# PasswordKeeper.net
KiCad netlist of a schematic drawn in EAGLE
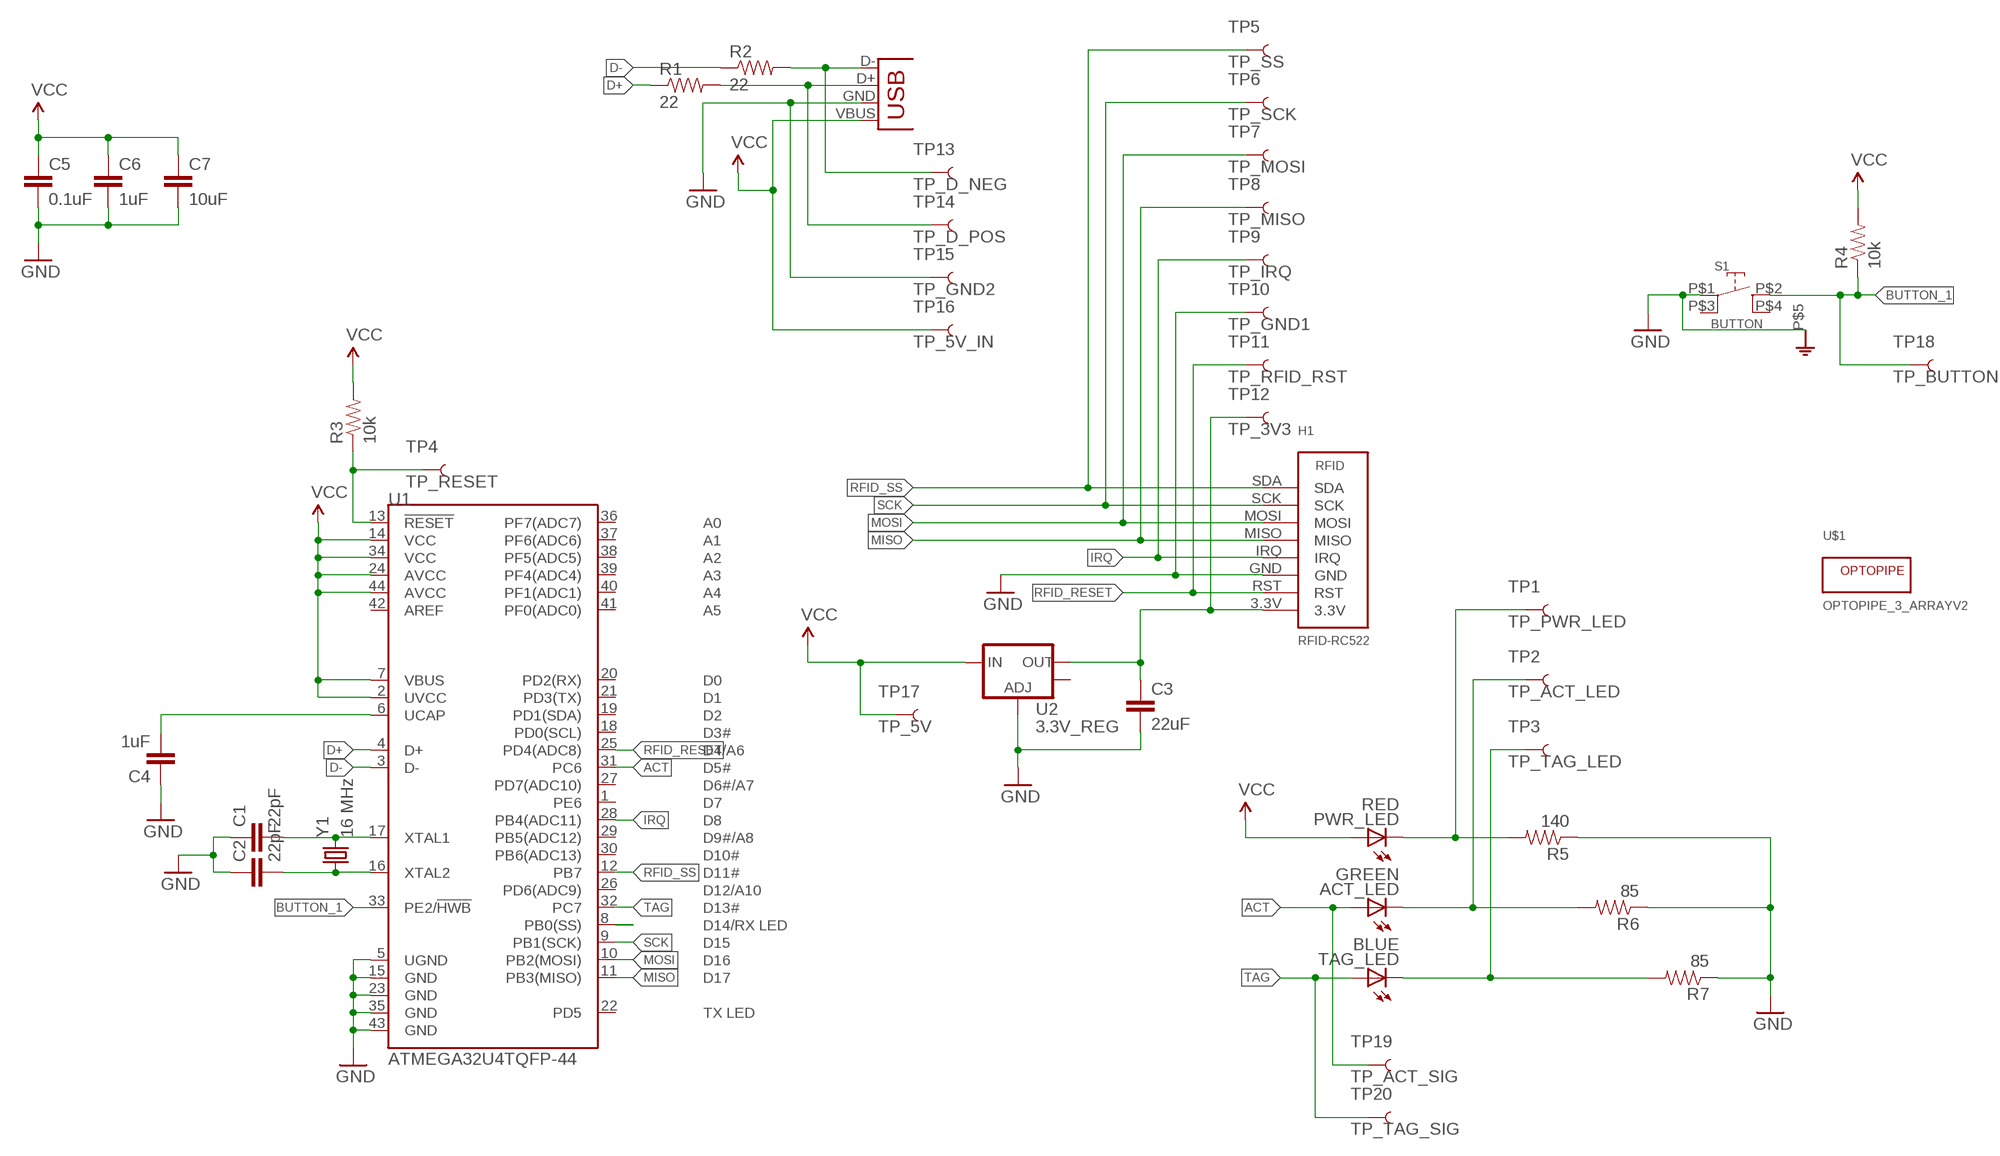
[diagram p0: schematic, sheet 1]

(export (version "E")
  (design (tool "Eeschema 10.0.6"))
  (components
    (comp (ref "ACT_LED")
      (value "GREEN")
      (footprint "eagle-import:LED-1206")
      (libsource (lib "eagle-import") (part "LED1206"))
    )
    (comp (ref "C1")
      (value "22pF")
      (footprint "eagle-import:1206")
      (libsource (lib "eagle-import") (part "CAP1206"))
    )
    (comp (ref "C2")
      (value "22pF")
      (footprint "eagle-import:1206")
      (libsource (lib "eagle-import") (part "CAP1206"))
    )
    (comp (ref "C3")
      (value "22uF")
      (footprint "eagle-import:0805")
      (libsource (lib "eagle-import") (part "22UF-0805-6.3V-20%"))
    )
    (comp (ref "C4")
      (value "1uF")
      (footprint "eagle-import:1206")
      (libsource (lib "eagle-import") (part "CAP1206"))
    )
    (comp (ref "C5")
      (value "0.1uF")
      (footprint "eagle-import:1206")
      (libsource (lib "eagle-import") (part "CAP1206"))
    )
    (comp (ref "C6")
      (value "1uF")
      (footprint "eagle-import:1206")
      (libsource (lib "eagle-import") (part "CAP1206"))
    )
    (comp (ref "C7")
      (value "10uF")
      (footprint "eagle-import:1206")
      (libsource (lib "eagle-import") (part "CAP1206"))
    )
    (comp (ref "H1")
      (value "RFID-RC522")
      (footprint "eagle-import:EXT_RFID_READER")
      (libsource (lib "eagle-import") (part "RFID-RC522"))
    )
    (comp (ref "JP1")
      (value "USB-A-H")
      (footprint "eagle-import:USB-A-H")
      (libsource (lib "eagle-import") (part "USB-A-H"))
    )
    (comp (ref "PWR_LED")
      (value "RED")
      (footprint "eagle-import:LED-1206")
      (libsource (lib "eagle-import") (part "LED1206"))
    )
    (comp (ref "R1")
      (value "22")
      (footprint "eagle-import:1206")
      (libsource (lib "eagle-import") (part "RESISTOR1206"))
    )
    (comp (ref "R2")
      (value "22")
      (footprint "eagle-import:1206")
      (libsource (lib "eagle-import") (part "RESISTOR1206"))
    )
    (comp (ref "R3")
      (value "10k")
      (footprint "eagle-import:1206")
      (libsource (lib "eagle-import") (part "RESISTOR1206"))
    )
    (comp (ref "R4")
      (value "10k")
      (footprint "eagle-import:1206")
      (libsource (lib "eagle-import") (part "RESISTOR1206"))
    )
    (comp (ref "R5")
      (value "140")
      (footprint "eagle-import:1206")
      (libsource (lib "eagle-import") (part "RESISTOR1206"))
    )
    (comp (ref "R6")
      (value "85")
      (footprint "eagle-import:1206")
      (libsource (lib "eagle-import") (part "RESISTOR1206"))
    )
    (comp (ref "R7")
      (value "85")
      (footprint "eagle-import:1206")
      (libsource (lib "eagle-import") (part "RESISTOR1206"))
    )
    (comp (ref "S1")
      (value "BUTTON")
      (footprint "eagle-import:TACTILE_SWITCH_SMD_RIGHT_ANGLE")
      (libsource (lib "eagle-import") (part "TACTILE_SWITCH_MOMENTARY_RIGHT_ANGLE"))
    )
    (comp (ref "TAG_LED")
      (value "BLUE")
      (footprint "eagle-import:LED-1206")
      (libsource (lib "eagle-import") (part "LED1206"))
    )
    (comp (ref "TP1")
      (value "TP_PWR_LED")
      (footprint "eagle-import:TP_15TH")
      (libsource (lib "eagle-import") (part "TEST-POINTTP_15TH_THRU"))
    )
    (comp (ref "TP2")
      (value "TP_ACT_LED")
      (footprint "eagle-import:TP_15TH")
      (libsource (lib "eagle-import") (part "TEST-POINTTP_15TH_THRU"))
    )
    (comp (ref "TP3")
      (value "TP_TAG_LED")
      (footprint "eagle-import:TP_15TH")
      (libsource (lib "eagle-import") (part "TEST-POINTTP_15TH_THRU"))
    )
    (comp (ref "TP4")
      (value "TP_RESET")
      (footprint "eagle-import:TP_15TH")
      (libsource (lib "eagle-import") (part "TEST-POINTTP_15TH_THRU"))
    )
    (comp (ref "TP5")
      (value "TP_SS")
      (footprint "eagle-import:TP_15TH")
      (libsource (lib "eagle-import") (part "TEST-POINTTP_15TH_THRU"))
    )
    (comp (ref "TP6")
      (value "TP_SCK")
      (footprint "eagle-import:TP_15TH")
      (libsource (lib "eagle-import") (part "TEST-POINTTP_15TH_THRU"))
    )
    (comp (ref "TP7")
      (value "TP_MOSI")
      (footprint "eagle-import:TP_15TH")
      (libsource (lib "eagle-import") (part "TEST-POINTTP_15TH_THRU"))
    )
    (comp (ref "TP8")
      (value "TP_MISO")
      (footprint "eagle-import:TP_15TH")
      (libsource (lib "eagle-import") (part "TEST-POINTTP_15TH_THRU"))
    )
    (comp (ref "TP9")
      (value "TP_IRQ")
      (footprint "eagle-import:TP_15TH")
      (libsource (lib "eagle-import") (part "TEST-POINTTP_15TH_THRU"))
    )
    (comp (ref "TP10")
      (value "TP_GND1")
      (footprint "eagle-import:TP_15TH")
      (libsource (lib "eagle-import") (part "TEST-POINTTP_15TH_THRU"))
    )
    (comp (ref "TP11")
      (value "TP_RFID_RST")
      (footprint "eagle-import:TP_15TH")
      (libsource (lib "eagle-import") (part "TEST-POINTTP_15TH_THRU"))
    )
    (comp (ref "TP12")
      (value "TP_3V3")
      (footprint "eagle-import:TP_15TH")
      (libsource (lib "eagle-import") (part "TEST-POINTTP_15TH_THRU"))
    )
    (comp (ref "TP13")
      (value "TP_D_NEG")
      (footprint "eagle-import:TP_15TH")
      (libsource (lib "eagle-import") (part "TEST-POINTTP_15TH_THRU"))
    )
    (comp (ref "TP14")
      (value "TP_D_POS")
      (footprint "eagle-import:TP_15TH")
      (libsource (lib "eagle-import") (part "TEST-POINTTP_15TH_THRU"))
    )
    (comp (ref "TP15")
      (value "TP_GND2")
      (footprint "eagle-import:TP_15TH")
      (libsource (lib "eagle-import") (part "TEST-POINTTP_15TH_THRU"))
    )
    (comp (ref "TP16")
      (value "TP_5V_IN")
      (footprint "eagle-import:TP_15TH")
      (libsource (lib "eagle-import") (part "TEST-POINTTP_15TH_THRU"))
    )
    (comp (ref "TP17")
      (value "TP_5V")
      (footprint "eagle-import:TP_15TH")
      (libsource (lib "eagle-import") (part "TEST-POINTTP_15TH_THRU"))
    )
    (comp (ref "TP18")
      (value "TP_BUTTON")
      (footprint "eagle-import:TP_15TH")
      (libsource (lib "eagle-import") (part "TEST-POINTTP_15TH_THRU"))
    )
    (comp (ref "TP19")
      (value "TP_ACT_SIG")
      (footprint "eagle-import:TP_15TH")
      (libsource (lib "eagle-import") (part "TEST-POINTTP_15TH_THRU"))
    )
    (comp (ref "TP20")
      (value "TP_TAG_SIG")
      (footprint "eagle-import:TP_15TH")
      (libsource (lib "eagle-import") (part "TEST-POINTTP_15TH_THRU"))
    )
    (comp (ref "U$1")
      (value "OPTOPIPE_3_ARRAYV2")
      (footprint "eagle-import:515-1000_V2")
      (libsource (lib "eagle-import") (part "OPTOPIPE_3_ARRAYV2"))
    )
    (comp (ref "U1")
      (value "ATMEGA32U4TQFP-44")
      (footprint "eagle-import:TQFP44")
      (libsource (lib "eagle-import") (part "ATMEGA32U4TQFP-44"))
    )
    (comp (ref "U2")
      (value "3.3V_REG")
      (footprint "eagle-import:SOT223")
      (libsource (lib "eagle-import") (part "V_REG_LM1117SOT223"))
    )
    (comp (ref "Y1")
      (value "16 MHz")
      (footprint "eagle-import:HC49UP")
      (libsource (lib "eagle-import") (part "CRYSTALSMD"))
    )
  )
  (nets
    (net (code "1") (name "ACT") (class "Default")
      (node (ref "ACT_LED") (pin "A") (pinfunction "A_A") (pintype "passive"))
      (node (ref "TP19") (pin "P$1") (pinfunction "1_P$1") (pintype "bidirectional"))
      (node (ref "U1") (pin "31") (pinfunction "PC6_31") (pintype "bidirectional"))
    )
    (net (code "2") (name "BUTTON_1") (class "Default")
      (node (ref "R4") (pin "1") (pinfunction "1_1") (pintype "passive"))
      (node (ref "S1") (pin "P$2") (pinfunction "P$2_P$2") (pintype "passive"))
      (node (ref "TP18") (pin "P$1") (pinfunction "1_P$1") (pintype "bidirectional"))
      (node (ref "U1") (pin "33") (pinfunction "PE2/~{HWB}_33") (pintype "bidirectional"))
    )
    (net (code "3") (name "D+") (class "Default")
      (node (ref "R1") (pin "1") (pinfunction "1_1") (pintype "passive"))
      (node (ref "U1") (pin "4") (pinfunction "D+_4") (pintype "bidirectional"))
    )
    (net (code "4") (name "D-") (class "Default")
      (node (ref "R2") (pin "1") (pinfunction "1_1") (pintype "passive"))
      (node (ref "U1") (pin "3") (pinfunction "D-_3") (pintype "bidirectional"))
    )
    (net (code "5") (name "GND") (class "Default")
      (node (ref "C1") (pin "1") (pinfunction "1_1") (pintype "passive"))
      (node (ref "C2") (pin "1") (pinfunction "1_1") (pintype "passive"))
      (node (ref "C3") (pin "2") (pinfunction "2_2") (pintype "passive"))
      (node (ref "C4") (pin "1") (pinfunction "1_1") (pintype "passive"))
      (node (ref "C5") (pin "2") (pinfunction "2_2") (pintype "passive"))
      (node (ref "C6") (pin "2") (pinfunction "2_2") (pintype "passive"))
      (node (ref "C7") (pin "2") (pinfunction "2_2") (pintype "passive"))
      (node (ref "H1") (pin "GND") (pinfunction "GND_GND") (pintype "bidirectional"))
      (node (ref "JP1") (pin "GND") (pinfunction "VBUS_GND") (pintype "bidirectional"))
      (node (ref "R5") (pin "1") (pinfunction "1_1") (pintype "passive"))
      (node (ref "R6") (pin "1") (pinfunction "1_1") (pintype "passive"))
      (node (ref "R7") (pin "1") (pinfunction "1_1") (pintype "passive"))
      (node (ref "S1") (pin "P$1") (pinfunction "P$1_P$1") (pintype "passive"))
      (node (ref "S1") (pin "P$5") (pinfunction "P$5_P$5") (pintype "bidirectional"))
      (node (ref "TP10") (pin "P$1") (pinfunction "1_P$1") (pintype "bidirectional"))
      (node (ref "TP15") (pin "P$1") (pinfunction "1_P$1") (pintype "bidirectional"))
      (node (ref "U1") (pin "15") (pinfunction "GND_15") (pintype "bidirectional"))
      (node (ref "U1") (pin "23") (pinfunction "GND_23") (pintype "bidirectional"))
      (node (ref "U1") (pin "35") (pinfunction "GND_35") (pintype "bidirectional"))
      (node (ref "U1") (pin "43") (pinfunction "GND_43") (pintype "bidirectional"))
      (node (ref "U1") (pin "5") (pinfunction "UGND_5") (pintype "bidirectional"))
      (node (ref "U2") (pin "1") (pinfunction "ADJ_1") (pintype "input"))
    )
    (net (code "6") (name "IRQ") (class "Default")
      (node (ref "H1") (pin "IRQ") (pinfunction "IRQ_IRQ") (pintype "bidirectional"))
      (node (ref "TP9") (pin "P$1") (pinfunction "1_P$1") (pintype "bidirectional"))
      (node (ref "U1") (pin "28") (pinfunction "PB4(ADC11)_28") (pintype "bidirectional"))
    )
    (net (code "7") (name "MISO") (class "Default")
      (node (ref "H1") (pin "MISO") (pinfunction "MISO_MISO") (pintype "bidirectional"))
      (node (ref "TP8") (pin "P$1") (pinfunction "1_P$1") (pintype "bidirectional"))
      (node (ref "U1") (pin "11") (pinfunction "PB3(MISO)_11") (pintype "bidirectional"))
    )
    (net (code "8") (name "MOSI") (class "Default")
      (node (ref "H1") (pin "MOSI") (pinfunction "MOSI_MOSI") (pintype "bidirectional"))
      (node (ref "TP7") (pin "P$1") (pinfunction "1_P$1") (pintype "bidirectional"))
      (node (ref "U1") (pin "10") (pinfunction "PB2(MOSI)_10") (pintype "bidirectional"))
    )
    (net (code "9") (name "Net-(JP1-D+)") (class "Default")
      (node (ref "JP1") (pin "D-") (pinfunction "D+_D-") (pintype "bidirectional"))
      (node (ref "R2") (pin "2") (pinfunction "2_2") (pintype "passive"))
      (node (ref "TP13") (pin "P$1") (pinfunction "1_P$1") (pintype "bidirectional"))
    )
    (net (code "10") (name "Net-(JP1-D-)") (class "Default")
      (node (ref "JP1") (pin "D+") (pinfunction "D-_D+") (pintype "bidirectional"))
      (node (ref "R1") (pin "2") (pinfunction "2_2") (pintype "passive"))
      (node (ref "TP14") (pin "P$1") (pinfunction "1_P$1") (pintype "bidirectional"))
    )
    (net (code "11") (name "Net-(TP1-1)") (class "Default")
      (node (ref "PWR_LED") (pin "C") (pinfunction "C_C") (pintype "passive"))
      (node (ref "R5") (pin "2") (pinfunction "2_2") (pintype "passive"))
      (node (ref "TP1") (pin "P$1") (pinfunction "1_P$1") (pintype "bidirectional"))
    )
    (net (code "12") (name "Net-(TP2-1)") (class "Default")
      (node (ref "ACT_LED") (pin "C") (pinfunction "C_C") (pintype "passive"))
      (node (ref "R6") (pin "2") (pinfunction "2_2") (pintype "passive"))
      (node (ref "TP2") (pin "P$1") (pinfunction "1_P$1") (pintype "bidirectional"))
    )
    (net (code "13") (name "Net-(TP3-1)") (class "Default")
      (node (ref "R7") (pin "2") (pinfunction "2_2") (pintype "passive"))
      (node (ref "TAG_LED") (pin "C") (pinfunction "C_C") (pintype "passive"))
      (node (ref "TP3") (pin "P$1") (pinfunction "1_P$1") (pintype "bidirectional"))
    )
    (net (code "14") (name "Net-(TP4-1)") (class "Default")
      (node (ref "R3") (pin "1") (pinfunction "1_1") (pintype "passive"))
      (node (ref "TP4") (pin "P$1") (pinfunction "1_P$1") (pintype "bidirectional"))
      (node (ref "U1") (pin "13") (pinfunction "~{RESET}_13") (pintype "bidirectional"))
    )
    (net (code "15") (name "Net-(TP12-1)") (class "Default")
      (node (ref "C3") (pin "1") (pinfunction "1_1") (pintype "passive"))
      (node (ref "H1") (pin "3.3V") (pinfunction "3.3V_3.3V") (pintype "bidirectional"))
      (node (ref "TP12") (pin "P$1") (pinfunction "1_P$1") (pintype "bidirectional"))
      (node (ref "U2") (pin "2") (pinfunction "OUT_2") (pintype "output"))
    )
    (net (code "16") (name "Net-(U1-UCAP)") (class "Default")
      (node (ref "C4") (pin "2") (pinfunction "2_2") (pintype "passive"))
      (node (ref "U1") (pin "6") (pinfunction "UCAP_6") (pintype "bidirectional"))
    )
    (net (code "17") (name "Net-(U1-XTAL1)") (class "Default")
      (node (ref "C1") (pin "2") (pinfunction "2_2") (pintype "passive"))
      (node (ref "U1") (pin "17") (pinfunction "XTAL1_17") (pintype "bidirectional"))
      (node (ref "Y1") (pin "2") (pinfunction "2_2") (pintype "passive"))
    )
    (net (code "18") (name "Net-(U1-XTAL2)") (class "Default")
      (node (ref "C2") (pin "2") (pinfunction "2_2") (pintype "passive"))
      (node (ref "U1") (pin "16") (pinfunction "XTAL2_16") (pintype "bidirectional"))
      (node (ref "Y1") (pin "1") (pinfunction "1_1") (pintype "passive"))
    )
    (net (code "19") (name "RFID_RESET") (class "Default")
      (node (ref "H1") (pin "RST") (pinfunction "RST_RST") (pintype "bidirectional"))
      (node (ref "TP11") (pin "P$1") (pinfunction "1_P$1") (pintype "bidirectional"))
      (node (ref "U1") (pin "25") (pinfunction "PD4(ADC8)_25") (pintype "bidirectional"))
    )
    (net (code "20") (name "RFID_SS") (class "Default")
      (node (ref "H1") (pin "SDA") (pinfunction "SDA_SDA") (pintype "bidirectional"))
      (node (ref "TP5") (pin "P$1") (pinfunction "1_P$1") (pintype "bidirectional"))
      (node (ref "U1") (pin "12") (pinfunction "PB7_12") (pintype "bidirectional"))
    )
    (net (code "21") (name "SCK") (class "Default")
      (node (ref "H1") (pin "SCK") (pinfunction "SCK_SCK") (pintype "bidirectional"))
      (node (ref "TP6") (pin "P$1") (pinfunction "1_P$1") (pintype "bidirectional"))
      (node (ref "U1") (pin "9") (pinfunction "PB1(SCK)_9") (pintype "bidirectional"))
    )
    (net (code "22") (name "TAG") (class "Default")
      (node (ref "TAG_LED") (pin "A") (pinfunction "A_A") (pintype "passive"))
      (node (ref "TP20") (pin "P$1") (pinfunction "1_P$1") (pintype "bidirectional"))
      (node (ref "U1") (pin "32") (pinfunction "PC7_32") (pintype "bidirectional"))
    )
    (net (code "23") (name "VCC") (class "Default")
      (node (ref "C5") (pin "1") (pinfunction "1_1") (pintype "passive"))
      (node (ref "C6") (pin "1") (pinfunction "1_1") (pintype "passive"))
      (node (ref "C7") (pin "1") (pinfunction "1_1") (pintype "passive"))
      (node (ref "JP1") (pin "VBUS") (pinfunction "GND_VBUS") (pintype "bidirectional"))
      (node (ref "PWR_LED") (pin "A") (pinfunction "A_A") (pintype "passive"))
      (node (ref "R3") (pin "2") (pinfunction "2_2") (pintype "passive"))
      (node (ref "R4") (pin "2") (pinfunction "2_2") (pintype "passive"))
      (node (ref "TP16") (pin "P$1") (pinfunction "1_P$1") (pintype "bidirectional"))
      (node (ref "TP17") (pin "P$1") (pinfunction "1_P$1") (pintype "bidirectional"))
      (node (ref "U1") (pin "14") (pinfunction "VCC_14") (pintype "bidirectional"))
      (node (ref "U1") (pin "2") (pinfunction "UVCC_2") (pintype "bidirectional"))
      (node (ref "U1") (pin "24") (pinfunction "AVCC_24") (pintype "bidirectional"))
      (node (ref "U1") (pin "34") (pinfunction "VCC_34") (pintype "bidirectional"))
      (node (ref "U1") (pin "44") (pinfunction "AVCC_44") (pintype "bidirectional"))
      (node (ref "U1") (pin "7") (pinfunction "VBUS_7") (pintype "bidirectional"))
      (node (ref "U2") (pin "3") (pinfunction "IN_3") (pintype "input"))
    )
    (net (code "24") (name "unconnected-(S1-PadP$3)") (class "Default")
      (node (ref "S1") (pin "P$3") (pinfunction "P$3_P$3") (pintype "passive"))
    )
    (net (code "25") (name "unconnected-(S1-PadP$4)") (class "Default")
      (node (ref "S1") (pin "P$4") (pinfunction "P$4_P$4") (pintype "passive"))
    )
    (net (code "26") (name "unconnected-(U1-AREF-Pad42)") (class "Default")
      (node (ref "U1") (pin "42") (pinfunction "AREF_42") (pintype "bidirectional"))
    )
    (net (code "27") (name "unconnected-(U1-PB0(SS)-Pad8)") (class "Default")
      (node (ref "U1") (pin "8") (pinfunction "PB0(SS)_8") (pintype "bidirectional"))
    )
    (net (code "28") (name "unconnected-(U1-PB5(ADC12)-Pad29)") (class "Default")
      (node (ref "U1") (pin "29") (pinfunction "PB5(ADC12)_29") (pintype "bidirectional"))
    )
    (net (code "29") (name "unconnected-(U1-PB6(ADC13)-Pad30)") (class "Default")
      (node (ref "U1") (pin "30") (pinfunction "PB6(ADC13)_30") (pintype "bidirectional"))
    )
    (net (code "30") (name "unconnected-(U1-PD0(SCL)-Pad18)") (class "Default")
      (node (ref "U1") (pin "18") (pinfunction "PD0(SCL)_18") (pintype "bidirectional"))
    )
    (net (code "31") (name "unconnected-(U1-PD1(SDA)-Pad19)") (class "Default")
      (node (ref "U1") (pin "19") (pinfunction "PD1(SDA)_19") (pintype "bidirectional"))
    )
    (net (code "32") (name "unconnected-(U1-PD2(RX)-Pad20)") (class "Default")
      (node (ref "U1") (pin "20") (pinfunction "PD2(RX)_20") (pintype "bidirectional"))
    )
    (net (code "33") (name "unconnected-(U1-PD3(TX)-Pad21)") (class "Default")
      (node (ref "U1") (pin "21") (pinfunction "PD3(TX)_21") (pintype "bidirectional"))
    )
    (net (code "34") (name "unconnected-(U1-PD5-Pad22)") (class "Default")
      (node (ref "U1") (pin "22") (pinfunction "PD5_22") (pintype "bidirectional"))
    )
    (net (code "35") (name "unconnected-(U1-PD6(ADC9)-Pad26)") (class "Default")
      (node (ref "U1") (pin "26") (pinfunction "PD6(ADC9)_26") (pintype "bidirectional"))
    )
    (net (code "36") (name "unconnected-(U1-PD7(ADC10)-Pad27)") (class "Default")
      (node (ref "U1") (pin "27") (pinfunction "PD7(ADC10)_27") (pintype "bidirectional"))
    )
    (net (code "37") (name "unconnected-(U1-PE6-Pad1)") (class "Default")
      (node (ref "U1") (pin "1") (pinfunction "PE6_1") (pintype "bidirectional"))
    )
    (net (code "38") (name "unconnected-(U1-PF0(ADC0)-Pad41)") (class "Default")
      (node (ref "U1") (pin "41") (pinfunction "PF0(ADC0)_41") (pintype "bidirectional"))
    )
    (net (code "39") (name "unconnected-(U1-PF1(ADC1)-Pad40)") (class "Default")
      (node (ref "U1") (pin "40") (pinfunction "PF1(ADC1)_40") (pintype "bidirectional"))
    )
    (net (code "40") (name "unconnected-(U1-PF4(ADC4)-Pad39)") (class "Default")
      (node (ref "U1") (pin "39") (pinfunction "PF4(ADC4)_39") (pintype "bidirectional"))
    )
    (net (code "41") (name "unconnected-(U1-PF5(ADC5)-Pad38)") (class "Default")
      (node (ref "U1") (pin "38") (pinfunction "PF5(ADC5)_38") (pintype "bidirectional"))
    )
    (net (code "42") (name "unconnected-(U1-PF6(ADC6)-Pad37)") (class "Default")
      (node (ref "U1") (pin "37") (pinfunction "PF6(ADC6)_37") (pintype "bidirectional"))
    )
    (net (code "43") (name "unconnected-(U1-PF7(ADC7)-Pad36)") (class "Default")
      (node (ref "U1") (pin "36") (pinfunction "PF7(ADC7)_36") (pintype "bidirectional"))
    )
    (net (code "44") (name "unconnected-(U2-OUT-Pad4)") (class "Default")
      (node (ref "U2") (pin "4") (pinfunction "OUT_4") (pintype "output"))
    )
  )
)
